# board.net
KiCad netlist of a schematic drawn in EAGLE
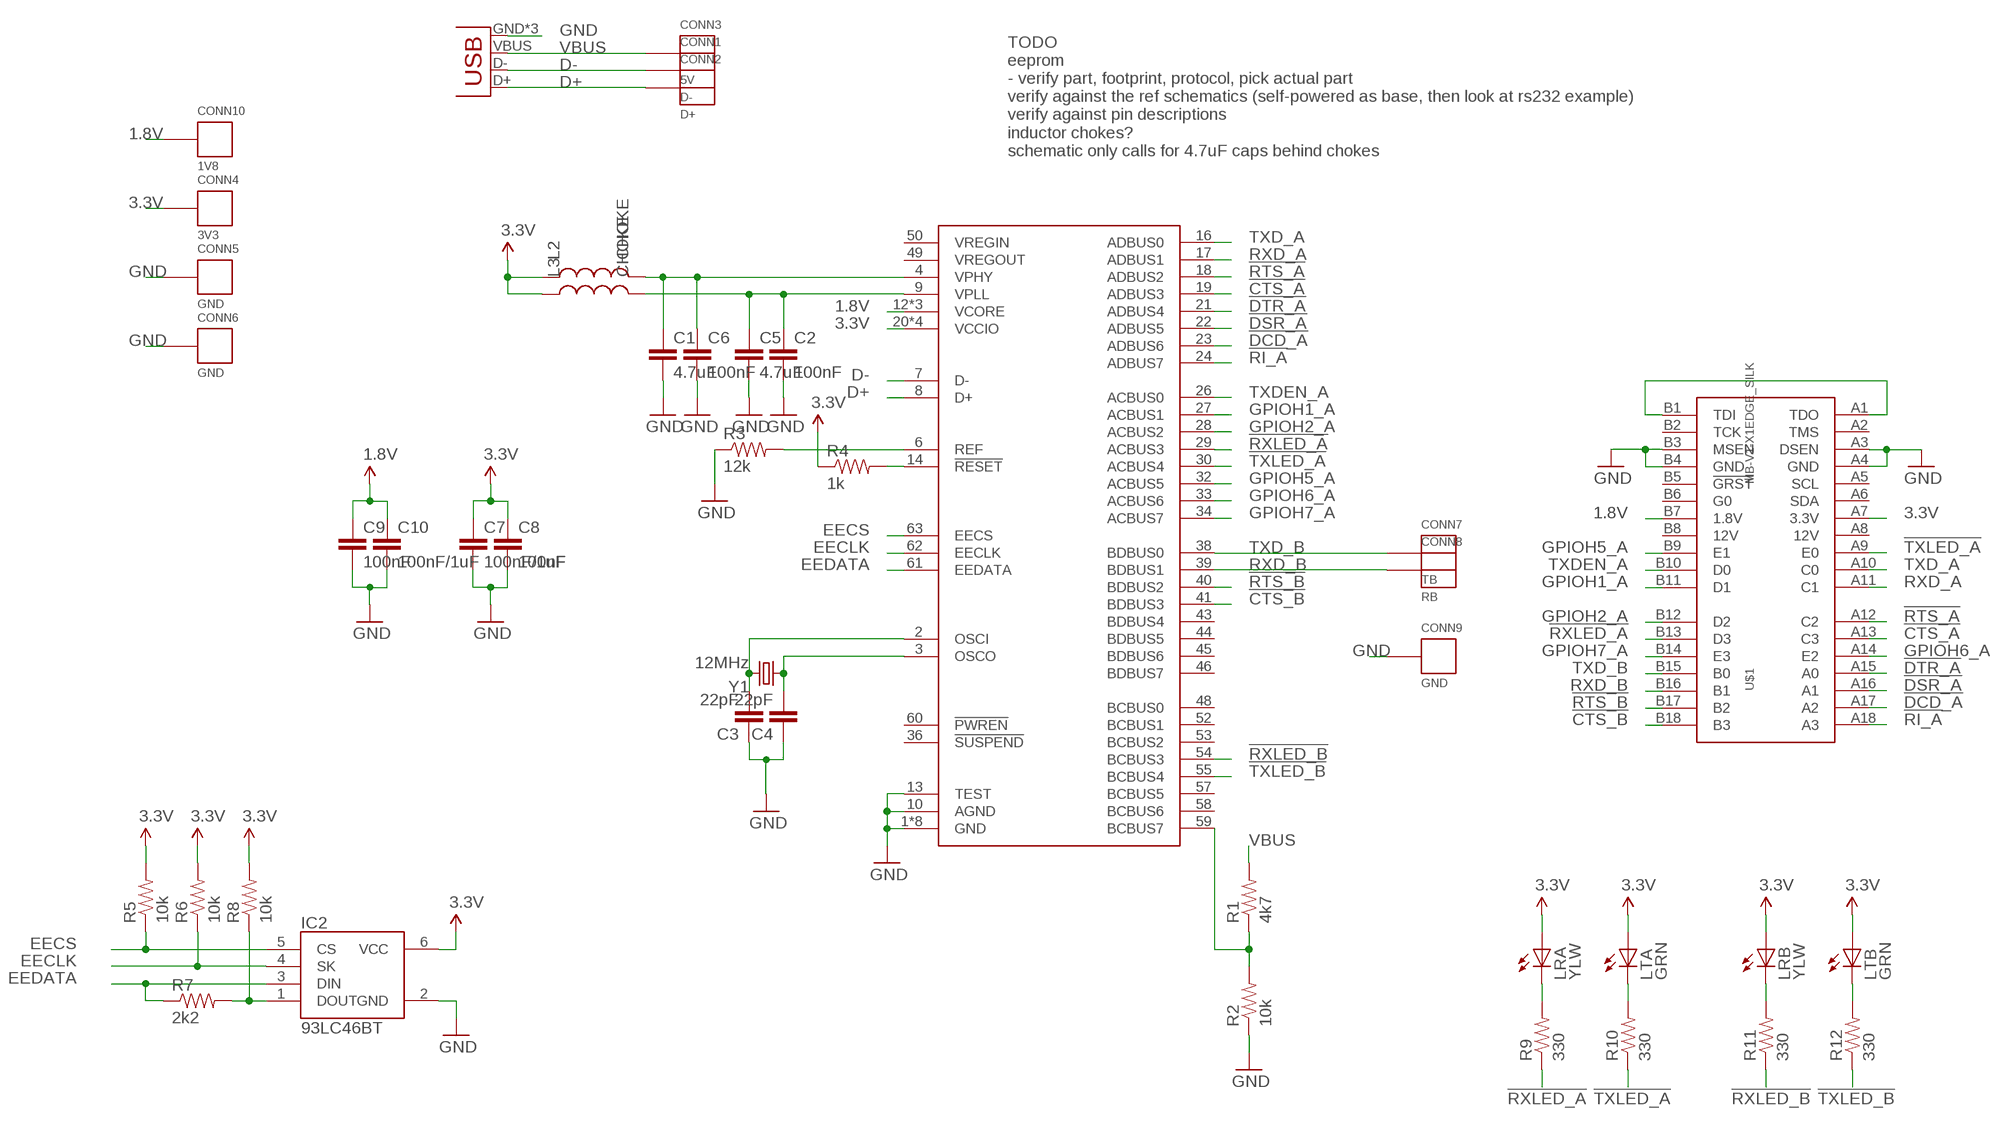
[diagram p0: schematic, sheet 1]

(export (version "E")
  (design (tool "Eeschema 10.0.6"))
  (components
    (comp (ref "C1")
      (value "4.7uF")
      (footprint "eagle-import:0805")
      (libsource (lib "eagle-import") (part "CAP0805"))
    )
    (comp (ref "C2")
      (value "100nF")
      (footprint "eagle-import:0402-CAP")
      (libsource (lib "eagle-import") (part "CAP0402-CAP"))
    )
    (comp (ref "C3")
      (value "22pF")
      (footprint "eagle-import:0402-CAP")
      (libsource (lib "eagle-import") (part "CAP0402-CAP"))
    )
    (comp (ref "C4")
      (value "22pF")
      (footprint "eagle-import:0402-CAP")
      (libsource (lib "eagle-import") (part "CAP0402-CAP"))
    )
    (comp (ref "C5")
      (value "4.7uF")
      (footprint "eagle-import:0805")
      (libsource (lib "eagle-import") (part "CAP0805"))
    )
    (comp (ref "C6")
      (value "100nF")
      (footprint "eagle-import:0402-CAP")
      (libsource (lib "eagle-import") (part "CAP0402-CAP"))
    )
    (comp (ref "C7")
      (value "100nF/1uF")
      (footprint "eagle-import:0402-CAP")
      (libsource (lib "eagle-import") (part "CAP0402-CAP"))
    )
    (comp (ref "C8")
      (value "100nF")
      (footprint "eagle-import:0402-CAP")
      (libsource (lib "eagle-import") (part "CAP0402-CAP"))
    )
    (comp (ref "C9")
      (value "100nF")
      (footprint "eagle-import:0402-CAP")
      (libsource (lib "eagle-import") (part "CAP0402-CAP"))
    )
    (comp (ref "C10")
      (value "100nF/1uF")
      (footprint "eagle-import:0402-CAP")
      (libsource (lib "eagle-import") (part "CAP0402-CAP"))
    )
    (comp (ref "CONN1")
      (value "D-")
      (footprint "eagle-import:TESTPAD-1.27")
      (libsource (lib "eagle-import") (part "CONNECTOR1.27"))
    )
    (comp (ref "CONN2")
      (value "D+")
      (footprint "eagle-import:TESTPAD-1.27")
      (libsource (lib "eagle-import") (part "CONNECTOR1.27"))
    )
    (comp (ref "CONN3")
      (value "5V")
      (footprint "eagle-import:TESTPAD-1.27")
      (libsource (lib "eagle-import") (part "CONNECTOR1.27"))
    )
    (comp (ref "CONN4")
      (value "3V3")
      (footprint "eagle-import:HOLE_22AWG")
      (libsource (lib "eagle-import") (part "CONNECTOR22AWG"))
    )
    (comp (ref "CONN5")
      (value "GND")
      (footprint "eagle-import:HOLE_22AWG")
      (libsource (lib "eagle-import") (part "CONNECTOR22AWG"))
    )
    (comp (ref "CONN6")
      (value "GND")
      (footprint "eagle-import:CLIP-AREA")
      (libsource (lib "eagle-import") (part "CONNECTORCLIP"))
    )
    (comp (ref "CONN7")
      (value "TB")
      (footprint "eagle-import:HOLE_22AWG")
      (libsource (lib "eagle-import") (part "CONNECTOR22AWG"))
    )
    (comp (ref "CONN8")
      (value "RB")
      (footprint "eagle-import:HOLE_22AWG")
      (libsource (lib "eagle-import") (part "CONNECTOR22AWG"))
    )
    (comp (ref "CONN9")
      (value "GND")
      (footprint "eagle-import:HOLE_22AWG")
      (libsource (lib "eagle-import") (part "CONNECTOR22AWG"))
    )
    (comp (ref "CONN10")
      (value "1V8")
      (footprint "eagle-import:HOLE_22AWG")
      (libsource (lib "eagle-import") (part "CONNECTOR22AWG"))
    )
    (comp (ref "IC1")
      (value "FT2232HL")
      (footprint "eagle-import:TQFP64_LONGPAD")
      (libsource (lib "eagle-import") (part "FT2232HL"))
    )
    (comp (ref "IC2")
      (value "93LC46BT")
      (footprint "eagle-import:SOT23-6L")
      (libsource (lib "eagle-import") (part "93C46SOT23-6"))
    )
    (comp (ref "JP2")
      (value "USBMICROB")
      (footprint "eagle-import:USB-MICROB")
      (libsource (lib "eagle-import") (part "USBMICROB"))
    )
    (comp (ref "L2")
      (value "CHOKE")
      (footprint "eagle-import:0603")
      (libsource (lib "eagle-import") (part "INDUCTOR0603"))
    )
    (comp (ref "L3")
      (value "CHOKE")
      (footprint "eagle-import:0603")
      (libsource (lib "eagle-import") (part "INDUCTOR0603"))
    )
    (comp (ref "LRA")
      (value "YLW")
      (footprint "eagle-import:0603_LED")
      (libsource (lib "eagle-import") (part "LED0603"))
    )
    (comp (ref "LRB")
      (value "YLW")
      (footprint "eagle-import:0603_LED")
      (libsource (lib "eagle-import") (part "LED0603"))
    )
    (comp (ref "LTA")
      (value "GRN")
      (footprint "eagle-import:0603_LED")
      (libsource (lib "eagle-import") (part "LED0603"))
    )
    (comp (ref "LTB")
      (value "GRN")
      (footprint "eagle-import:0603_LED")
      (libsource (lib "eagle-import") (part "LED0603"))
    )
    (comp (ref "R1")
      (value "4k7")
      (footprint "eagle-import:0603-RES")
      (libsource (lib "eagle-import") (part "RESISTOR0603"))
    )
    (comp (ref "R2")
      (value "10k")
      (footprint "eagle-import:0603-RES")
      (libsource (lib "eagle-import") (part "RESISTOR0603"))
    )
    (comp (ref "R3")
      (value "12k")
      (footprint "eagle-import:0603-RES")
      (libsource (lib "eagle-import") (part "RESISTOR0603"))
    )
    (comp (ref "R4")
      (value "1k")
      (footprint "eagle-import:0603-RES")
      (libsource (lib "eagle-import") (part "RESISTOR0603"))
    )
    (comp (ref "R5")
      (value "10k")
      (footprint "eagle-import:0603-RES")
      (libsource (lib "eagle-import") (part "RESISTOR0603"))
    )
    (comp (ref "R6")
      (value "10k")
      (footprint "eagle-import:0603-RES")
      (libsource (lib "eagle-import") (part "RESISTOR0603"))
    )
    (comp (ref "R7")
      (value "2k2")
      (footprint "eagle-import:0603-RES")
      (libsource (lib "eagle-import") (part "RESISTOR0603"))
    )
    (comp (ref "R8")
      (value "10k")
      (footprint "eagle-import:0603-RES")
      (libsource (lib "eagle-import") (part "RESISTOR0603"))
    )
    (comp (ref "R9")
      (value "330")
      (footprint "eagle-import:0603-RES")
      (libsource (lib "eagle-import") (part "RESISTOR0603"))
    )
    (comp (ref "R10")
      (value "330")
      (footprint "eagle-import:0603-RES")
      (libsource (lib "eagle-import") (part "RESISTOR0603"))
    )
    (comp (ref "R11")
      (value "330")
      (footprint "eagle-import:0603-RES")
      (libsource (lib "eagle-import") (part "RESISTOR0603"))
    )
    (comp (ref "R12")
      (value "330")
      (footprint "eagle-import:0603-RES")
      (libsource (lib "eagle-import") (part "RESISTOR0603"))
    )
    (comp (ref "U$1")
      (value "MB-V1-X1EDGE_SILK")
      (footprint "eagle-import:MB-V1-X1-EDGE")
      (libsource (lib "eagle-import") (part "MB-V1-X1EDGE_SILK"))
    )
    (comp (ref "Y1")
      (value "12MHz")
      (footprint "eagle-import:HC49US")
      (libsource (lib "eagle-import") (part "CRYSTALHC49US"))
    )
  )
  (nets
    (net (code "1") (name "/D+") (class "Default")
      (node (ref "CONN2") (pin "P") (pinfunction "P_P") (pintype "bidirectional"))
      (node (ref "IC1") (pin "8") (pinfunction "D+_8") (pintype "input"))
      (node (ref "JP2") (pin "D+") (pinfunction "D+_D+") (pintype "bidirectional"))
    )
    (net (code "2") (name "/D-") (class "Default")
      (node (ref "CONN1") (pin "P") (pinfunction "P_P") (pintype "bidirectional"))
      (node (ref "IC1") (pin "7") (pinfunction "D-_7") (pintype "input"))
      (node (ref "JP2") (pin "D-") (pinfunction "D-_D-") (pintype "bidirectional"))
    )
    (net (code "3") (name "/EECLK") (class "Default")
      (node (ref "IC1") (pin "62") (pinfunction "EECLK_62") (pintype "bidirectional"))
      (node (ref "IC2") (pin "4") (pinfunction "SK_4") (pintype "input"))
      (node (ref "R6") (pin "1") (pinfunction "1_1") (pintype "passive"))
    )
    (net (code "4") (name "/EECS") (class "Default")
      (node (ref "IC1") (pin "63") (pinfunction "EECS_63") (pintype "bidirectional"))
      (node (ref "IC2") (pin "5") (pinfunction "CS_5") (pintype "input"))
      (node (ref "R5") (pin "1") (pinfunction "1_1") (pintype "passive"))
    )
    (net (code "5") (name "/EEDATA") (class "Default")
      (node (ref "IC1") (pin "61") (pinfunction "EEDATA_61") (pintype "bidirectional"))
      (node (ref "IC2") (pin "3") (pinfunction "DIN_3") (pintype "input"))
      (node (ref "R7") (pin "1") (pinfunction "1_1") (pintype "passive"))
    )
    (net (code "6") (name "/GPIOH1_A") (class "Default")
      (node (ref "IC1") (pin "27") (pinfunction "ACBUS1_27") (pintype "bidirectional"))
      (node (ref "U$1") (pin "B11") (pinfunction "D1_B11") (pintype "bidirectional"))
    )
    (net (code "7") (name "/GPIOH2_A") (class "Default")
      (node (ref "IC1") (pin "28") (pinfunction "ACBUS2_28") (pintype "bidirectional"))
      (node (ref "U$1") (pin "B12") (pinfunction "D2_B12") (pintype "bidirectional"))
    )
    (net (code "8") (name "/GPIOH5_A") (class "Default")
      (node (ref "IC1") (pin "32") (pinfunction "ACBUS5_32") (pintype "bidirectional"))
      (node (ref "U$1") (pin "B9") (pinfunction "E1_B9") (pintype "bidirectional"))
    )
    (net (code "9") (name "/GPIOH6_A") (class "Default")
      (node (ref "IC1") (pin "33") (pinfunction "ACBUS6_33") (pintype "bidirectional"))
      (node (ref "U$1") (pin "A14") (pinfunction "E2_A14") (pintype "bidirectional"))
    )
    (net (code "10") (name "/GPIOH7_A") (class "Default")
      (node (ref "IC1") (pin "34") (pinfunction "ACBUS7_34") (pintype "bidirectional"))
      (node (ref "U$1") (pin "B14") (pinfunction "E3_B14") (pintype "bidirectional"))
    )
    (net (code "11") (name "/RXD_A") (class "Default")
      (node (ref "IC1") (pin "17") (pinfunction "ADBUS1_17") (pintype "bidirectional"))
      (node (ref "U$1") (pin "A11") (pinfunction "C1_A11") (pintype "bidirectional"))
    )
    (net (code "12") (name "/RXD_B") (class "Default")
      (node (ref "CONN8") (pin "P") (pinfunction "P_P") (pintype "bidirectional"))
      (node (ref "IC1") (pin "39") (pinfunction "BDBUS1_39") (pintype "bidirectional"))
      (node (ref "U$1") (pin "B16") (pinfunction "B1_B16") (pintype "bidirectional"))
    )
    (net (code "13") (name "/TXDEN_A") (class "Default")
      (node (ref "IC1") (pin "26") (pinfunction "ACBUS0_26") (pintype "bidirectional"))
      (node (ref "U$1") (pin "B10") (pinfunction "D0_B10") (pintype "bidirectional"))
    )
    (net (code "14") (name "/TXD_A") (class "Default")
      (node (ref "IC1") (pin "16") (pinfunction "ADBUS0_16") (pintype "bidirectional"))
      (node (ref "U$1") (pin "A10") (pinfunction "C0_A10") (pintype "bidirectional"))
    )
    (net (code "15") (name "/TXD_B") (class "Default")
      (node (ref "CONN7") (pin "P") (pinfunction "P_P") (pintype "bidirectional"))
      (node (ref "IC1") (pin "38") (pinfunction "BDBUS0_38") (pintype "bidirectional"))
      (node (ref "U$1") (pin "B15") (pinfunction "B0_B15") (pintype "bidirectional"))
    )
    (net (code "16") (name "/VBUS") (class "Default")
      (node (ref "CONN3") (pin "P") (pinfunction "P_P") (pintype "bidirectional"))
      (node (ref "JP2") (pin "VBUS") (pinfunction "VBUS_VBUS") (pintype "bidirectional"))
      (node (ref "R1") (pin "2") (pinfunction "2_2") (pintype "passive"))
    )
    (net (code "17") (name "/~{CTS_A}") (class "Default")
      (node (ref "IC1") (pin "19") (pinfunction "ADBUS3_19") (pintype "bidirectional"))
      (node (ref "U$1") (pin "A13") (pinfunction "C3_A13") (pintype "bidirectional"))
    )
    (net (code "18") (name "/~{CTS_B}") (class "Default")
      (node (ref "IC1") (pin "41") (pinfunction "BDBUS3_41") (pintype "bidirectional"))
      (node (ref "U$1") (pin "B18") (pinfunction "B3_B18") (pintype "bidirectional"))
    )
    (net (code "19") (name "/~{DCD_A}") (class "Default")
      (node (ref "IC1") (pin "23") (pinfunction "ADBUS6_23") (pintype "bidirectional"))
      (node (ref "U$1") (pin "A17") (pinfunction "A2_A17") (pintype "bidirectional"))
    )
    (net (code "20") (name "/~{DSR_A}") (class "Default")
      (node (ref "IC1") (pin "22") (pinfunction "ADBUS5_22") (pintype "bidirectional"))
      (node (ref "U$1") (pin "A16") (pinfunction "A1_A16") (pintype "bidirectional"))
    )
    (net (code "21") (name "/~{DTR_A}") (class "Default")
      (node (ref "IC1") (pin "21") (pinfunction "ADBUS4_21") (pintype "bidirectional"))
      (node (ref "U$1") (pin "A15") (pinfunction "A0_A15") (pintype "bidirectional"))
    )
    (net (code "22") (name "/~{RI_A}") (class "Default")
      (node (ref "IC1") (pin "24") (pinfunction "ADBUS7_24") (pintype "bidirectional"))
      (node (ref "U$1") (pin "A18") (pinfunction "A3_A18") (pintype "bidirectional"))
    )
    (net (code "23") (name "/~{RTS_A}") (class "Default")
      (node (ref "IC1") (pin "18") (pinfunction "ADBUS2_18") (pintype "bidirectional"))
      (node (ref "U$1") (pin "A12") (pinfunction "C2_A12") (pintype "bidirectional"))
    )
    (net (code "24") (name "/~{RTS_B}") (class "Default")
      (node (ref "IC1") (pin "40") (pinfunction "BDBUS2_40") (pintype "bidirectional"))
      (node (ref "U$1") (pin "B17") (pinfunction "B2_B17") (pintype "bidirectional"))
    )
    (net (code "25") (name "/~{RXLED_A}") (class "Default")
      (node (ref "IC1") (pin "29") (pinfunction "ACBUS3_29") (pintype "bidirectional"))
      (node (ref "R9") (pin "1") (pinfunction "1_1") (pintype "passive"))
      (node (ref "U$1") (pin "B13") (pinfunction "D3_B13") (pintype "bidirectional"))
    )
    (net (code "26") (name "/~{RXLED_B}") (class "Default")
      (node (ref "IC1") (pin "54") (pinfunction "BCBUS3_54") (pintype "bidirectional"))
      (node (ref "R11") (pin "1") (pinfunction "1_1") (pintype "passive"))
    )
    (net (code "27") (name "/~{TXLED_A}") (class "Default")
      (node (ref "IC1") (pin "30") (pinfunction "ACBUS4_30") (pintype "bidirectional"))
      (node (ref "R10") (pin "1") (pinfunction "1_1") (pintype "passive"))
      (node (ref "U$1") (pin "A9") (pinfunction "E0_A9") (pintype "bidirectional"))
    )
    (net (code "28") (name "/~{TXLED_B}") (class "Default")
      (node (ref "IC1") (pin "55") (pinfunction "BCBUS4_55") (pintype "bidirectional"))
      (node (ref "R12") (pin "1") (pinfunction "1_1") (pintype "passive"))
    )
    (net (code "29") (name "1.8V") (class "Default")
      (node (ref "C10") (pin "1") (pinfunction "1_1") (pintype "passive"))
      (node (ref "C9") (pin "1") (pinfunction "1_1") (pintype "passive"))
      (node (ref "CONN10") (pin "P") (pinfunction "P_P") (pintype "bidirectional"))
      (node (ref "IC1") (pin "12") (pinfunction "VCORE_12") (pintype "input"))
      (node (ref "IC1") (pin "37") (pinfunction "VCORE_37") (pintype "input"))
      (node (ref "IC1") (pin "64") (pinfunction "VCORE_64") (pintype "input"))
      (node (ref "U$1") (pin "B7") (pinfunction "1.8V_B7") (pintype "bidirectional"))
    )
    (net (code "30") (name "3.3V") (class "Default")
      (node (ref "C7") (pin "1") (pinfunction "1_1") (pintype "passive"))
      (node (ref "C8") (pin "1") (pinfunction "1_1") (pintype "passive"))
      (node (ref "CONN4") (pin "P") (pinfunction "P_P") (pintype "bidirectional"))
      (node (ref "IC1") (pin "20") (pinfunction "VCCIO_20") (pintype "input"))
      (node (ref "IC1") (pin "31") (pinfunction "VCCIO_31") (pintype "input"))
      (node (ref "IC1") (pin "42") (pinfunction "VCCIO_42") (pintype "input"))
      (node (ref "IC1") (pin "56") (pinfunction "VCCIO_56") (pintype "input"))
      (node (ref "IC2") (pin "6") (pinfunction "VCC_6") (pintype "input"))
      (node (ref "L2") (pin "1") (pinfunction "1_1") (pintype "passive"))
      (node (ref "L3") (pin "1") (pinfunction "1_1") (pintype "passive"))
      (node (ref "LRA") (pin "A") (pinfunction "A_A") (pintype "passive"))
      (node (ref "LRB") (pin "A") (pinfunction "A_A") (pintype "passive"))
      (node (ref "LTA") (pin "A") (pinfunction "A_A") (pintype "passive"))
      (node (ref "LTB") (pin "A") (pinfunction "A_A") (pintype "passive"))
      (node (ref "R4") (pin "1") (pinfunction "1_1") (pintype "passive"))
      (node (ref "R5") (pin "2") (pinfunction "2_2") (pintype "passive"))
      (node (ref "R6") (pin "2") (pinfunction "2_2") (pintype "passive"))
      (node (ref "R8") (pin "2") (pinfunction "2_2") (pintype "passive"))
      (node (ref "U$1") (pin "A7") (pinfunction "3.3V_A7") (pintype "bidirectional"))
    )
    (net (code "31") (name "GND") (class "Default")
      (node (ref "C1") (pin "2") (pinfunction "2_2") (pintype "passive"))
      (node (ref "C10") (pin "2") (pinfunction "2_2") (pintype "passive"))
      (node (ref "C2") (pin "2") (pinfunction "2_2") (pintype "passive"))
      (node (ref "C3") (pin "1") (pinfunction "1_1") (pintype "passive"))
      (node (ref "C4") (pin "1") (pinfunction "1_1") (pintype "passive"))
      (node (ref "C5") (pin "2") (pinfunction "2_2") (pintype "passive"))
      (node (ref "C6") (pin "2") (pinfunction "2_2") (pintype "passive"))
      (node (ref "C7") (pin "2") (pinfunction "2_2") (pintype "passive"))
      (node (ref "C8") (pin "2") (pinfunction "2_2") (pintype "passive"))
      (node (ref "C9") (pin "2") (pinfunction "2_2") (pintype "passive"))
      (node (ref "CONN5") (pin "P") (pinfunction "P_P") (pintype "bidirectional"))
      (node (ref "CONN6") (pin "P$1") (pinfunction "P_P$1") (pintype "bidirectional"))
      (node (ref "CONN6") (pin "P$2") (pinfunction "P_P$2") (pintype "bidirectional"))
      (node (ref "CONN9") (pin "P") (pinfunction "P_P") (pintype "bidirectional"))
      (node (ref "IC1") (pin "1") (pinfunction "GND_1") (pintype "input"))
      (node (ref "IC1") (pin "10") (pinfunction "AGND_10") (pintype "input"))
      (node (ref "IC1") (pin "11") (pinfunction "GND_11") (pintype "input"))
      (node (ref "IC1") (pin "13") (pinfunction "TEST_13") (pintype "input"))
      (node (ref "IC1") (pin "15") (pinfunction "GND_15") (pintype "input"))
      (node (ref "IC1") (pin "25") (pinfunction "GND_25") (pintype "input"))
      (node (ref "IC1") (pin "35") (pinfunction "GND_35") (pintype "input"))
      (node (ref "IC1") (pin "47") (pinfunction "GND_47") (pintype "input"))
      (node (ref "IC1") (pin "5") (pinfunction "GND_5") (pintype "input"))
      (node (ref "IC1") (pin "51") (pinfunction "GND_51") (pintype "input"))
      (node (ref "IC2") (pin "2") (pinfunction "GND_2") (pintype "input"))
      (node (ref "JP2") (pin "GND") (pinfunction "GND_GND") (pintype "bidirectional"))
      (node (ref "JP2") (pin "MT1") (pinfunction "GND_MT1") (pintype "bidirectional"))
      (node (ref "JP2") (pin "MT2") (pinfunction "GND_MT2") (pintype "bidirectional"))
      (node (ref "R2") (pin "1") (pinfunction "1_1") (pintype "passive"))
      (node (ref "R3") (pin "1") (pinfunction "1_1") (pintype "passive"))
      (node (ref "U$1") (pin "A3") (pinfunction "DSEN_A3") (pintype "bidirectional"))
      (node (ref "U$1") (pin "A4") (pinfunction "GND_A4") (pintype "bidirectional"))
      (node (ref "U$1") (pin "B3") (pinfunction "MSEN_B3") (pintype "bidirectional"))
      (node (ref "U$1") (pin "B4") (pinfunction "GND_B4") (pintype "bidirectional"))
    )
    (net (code "32") (name "Net-(IC1-BCBUS7)") (class "Default")
      (node (ref "IC1") (pin "59") (pinfunction "BCBUS7_59") (pintype "bidirectional"))
      (node (ref "R1") (pin "1") (pinfunction "1_1") (pintype "passive"))
      (node (ref "R2") (pin "2") (pinfunction "2_2") (pintype "passive"))
    )
    (net (code "33") (name "Net-(IC1-OSCI)") (class "Default")
      (node (ref "C3") (pin "2") (pinfunction "2_2") (pintype "passive"))
      (node (ref "IC1") (pin "2") (pinfunction "OSCI_2") (pintype "input"))
      (node (ref "Y1") (pin "2") (pinfunction "2_2") (pintype "passive"))
    )
    (net (code "34") (name "Net-(IC1-OSCO)") (class "Default")
      (node (ref "C4") (pin "2") (pinfunction "2_2") (pintype "passive"))
      (node (ref "IC1") (pin "3") (pinfunction "OSCO_3") (pintype "bidirectional"))
      (node (ref "Y1") (pin "1") (pinfunction "1_1") (pintype "passive"))
    )
    (net (code "35") (name "Net-(IC1-REF)") (class "Default")
      (node (ref "IC1") (pin "6") (pinfunction "REF_6") (pintype "input"))
      (node (ref "R3") (pin "2") (pinfunction "2_2") (pintype "passive"))
    )
    (net (code "36") (name "Net-(IC1-VPHY)") (class "Default")
      (node (ref "C1") (pin "1") (pinfunction "1_1") (pintype "passive"))
      (node (ref "C6") (pin "1") (pinfunction "1_1") (pintype "passive"))
      (node (ref "IC1") (pin "4") (pinfunction "VPHY_4") (pintype "input"))
      (node (ref "L2") (pin "2") (pinfunction "2_2") (pintype "passive"))
    )
    (net (code "37") (name "Net-(IC1-VPLL)") (class "Default")
      (node (ref "C2") (pin "1") (pinfunction "1_1") (pintype "passive"))
      (node (ref "C5") (pin "1") (pinfunction "1_1") (pintype "passive"))
      (node (ref "IC1") (pin "9") (pinfunction "VPLL_9") (pintype "input"))
      (node (ref "L3") (pin "2") (pinfunction "2_2") (pintype "passive"))
    )
    (net (code "38") (name "Net-(IC1-~{RESET})") (class "Default")
      (node (ref "IC1") (pin "14") (pinfunction "~{RESET}_14") (pintype "input"))
      (node (ref "R4") (pin "2") (pinfunction "2_2") (pintype "passive"))
    )
    (net (code "39") (name "Net-(IC2-DOUT)") (class "Default")
      (node (ref "IC2") (pin "1") (pinfunction "DOUT_1") (pintype "bidirectional"))
      (node (ref "R7") (pin "2") (pinfunction "2_2") (pintype "passive"))
      (node (ref "R8") (pin "1") (pinfunction "1_1") (pintype "passive"))
    )
    (net (code "40") (name "Net-(LRA-PadC)") (class "Default")
      (node (ref "LRA") (pin "C") (pinfunction "C_C") (pintype "passive"))
      (node (ref "R9") (pin "2") (pinfunction "2_2") (pintype "passive"))
    )
    (net (code "41") (name "Net-(LRB-PadC)") (class "Default")
      (node (ref "LRB") (pin "C") (pinfunction "C_C") (pintype "passive"))
      (node (ref "R11") (pin "2") (pinfunction "2_2") (pintype "passive"))
    )
    (net (code "42") (name "Net-(LTA-PadC)") (class "Default")
      (node (ref "LTA") (pin "C") (pinfunction "C_C") (pintype "passive"))
      (node (ref "R10") (pin "2") (pinfunction "2_2") (pintype "passive"))
    )
    (net (code "43") (name "Net-(LTB-PadC)") (class "Default")
      (node (ref "LTB") (pin "C") (pinfunction "C_C") (pintype "passive"))
      (node (ref "R12") (pin "2") (pinfunction "2_2") (pintype "passive"))
    )
    (net (code "44") (name "Net-(U$1-TDI)") (class "Default")
      (node (ref "U$1") (pin "A1") (pinfunction "TDO_A1") (pintype "bidirectional"))
      (node (ref "U$1") (pin "B1") (pinfunction "TDI_B1") (pintype "bidirectional"))
    )
    (net (code "45") (name "unconnected-(IC1-BCBUS0-Pad48)") (class "Default")
      (node (ref "IC1") (pin "48") (pinfunction "BCBUS0_48") (pintype "bidirectional"))
    )
    (net (code "46") (name "unconnected-(IC1-BCBUS1-Pad52)") (class "Default")
      (node (ref "IC1") (pin "52") (pinfunction "BCBUS1_52") (pintype "bidirectional"))
    )
    (net (code "47") (name "unconnected-(IC1-BCBUS2-Pad53)") (class "Default")
      (node (ref "IC1") (pin "53") (pinfunction "BCBUS2_53") (pintype "bidirectional"))
    )
    (net (code "48") (name "unconnected-(IC1-BCBUS5-Pad57)") (class "Default")
      (node (ref "IC1") (pin "57") (pinfunction "BCBUS5_57") (pintype "bidirectional"))
    )
    (net (code "49") (name "unconnected-(IC1-BCBUS6-Pad58)") (class "Default")
      (node (ref "IC1") (pin "58") (pinfunction "BCBUS6_58") (pintype "bidirectional"))
    )
    (net (code "50") (name "unconnected-(IC1-BDBUS4-Pad43)") (class "Default")
      (node (ref "IC1") (pin "43") (pinfunction "BDBUS4_43") (pintype "bidirectional"))
    )
    (net (code "51") (name "unconnected-(IC1-BDBUS5-Pad44)") (class "Default")
      (node (ref "IC1") (pin "44") (pinfunction "BDBUS5_44") (pintype "bidirectional"))
    )
    (net (code "52") (name "unconnected-(IC1-BDBUS6-Pad45)") (class "Default")
      (node (ref "IC1") (pin "45") (pinfunction "BDBUS6_45") (pintype "bidirectional"))
    )
    (net (code "53") (name "unconnected-(IC1-BDBUS7-Pad46)") (class "Default")
      (node (ref "IC1") (pin "46") (pinfunction "BDBUS7_46") (pintype "bidirectional"))
    )
    (net (code "54") (name "unconnected-(IC1-VREGIN-Pad50)") (class "Default")
      (node (ref "IC1") (pin "50") (pinfunction "VREGIN_50") (pintype "bidirectional"))
    )
    (net (code "55") (name "unconnected-(IC1-VREGOUT-Pad49)") (class "Default")
      (node (ref "IC1") (pin "49") (pinfunction "VREGOUT_49") (pintype "output"))
    )
    (net (code "56") (name "unconnected-(IC1-~{PWREN}-Pad60)") (class "Default")
      (node (ref "IC1") (pin "60") (pinfunction "~{PWREN}_60") (pintype "output"))
    )
    (net (code "57") (name "unconnected-(IC1-~{SUSPEND}-Pad36)") (class "Default")
      (node (ref "IC1") (pin "36") (pinfunction "~{SUSPEND}_36") (pintype "output"))
    )
    (net (code "58") (name "unconnected-(U$1-12V-PadA8)") (class "Default")
      (node (ref "U$1") (pin "A8") (pinfunction "12V_A8") (pintype "bidirectional"))
    )
    (net (code "59") (name "unconnected-(U$1-12V-PadB8)") (class "Default")
      (node (ref "U$1") (pin "B8") (pinfunction "12V_B8") (pintype "bidirectional"))
    )
    (net (code "60") (name "unconnected-(U$1-G0-PadB6)") (class "Default")
      (node (ref "U$1") (pin "B6") (pinfunction "G0_B6") (pintype "bidirectional"))
    )
    (net (code "61") (name "unconnected-(U$1-SCL-PadA5)") (class "Default")
      (node (ref "U$1") (pin "A5") (pinfunction "SCL_A5") (pintype "bidirectional"))
    )
    (net (code "62") (name "unconnected-(U$1-SDA-PadA6)") (class "Default")
      (node (ref "U$1") (pin "A6") (pinfunction "SDA_A6") (pintype "bidirectional"))
    )
    (net (code "63") (name "unconnected-(U$1-TCK-PadB2)") (class "Default")
      (node (ref "U$1") (pin "B2") (pinfunction "TCK_B2") (pintype "bidirectional"))
    )
    (net (code "64") (name "unconnected-(U$1-TMS-PadA2)") (class "Default")
      (node (ref "U$1") (pin "A2") (pinfunction "TMS_A2") (pintype "bidirectional"))
    )
    (net (code "65") (name "unconnected-(U$1-~{GRST}-PadB5)") (class "Default")
      (node (ref "U$1") (pin "B5") (pinfunction "~{GRST}_B5") (pintype "bidirectional"))
    )
  )
)
